# TopLevel.net
KiCad netlist of a schematic drawn in Altium Designer
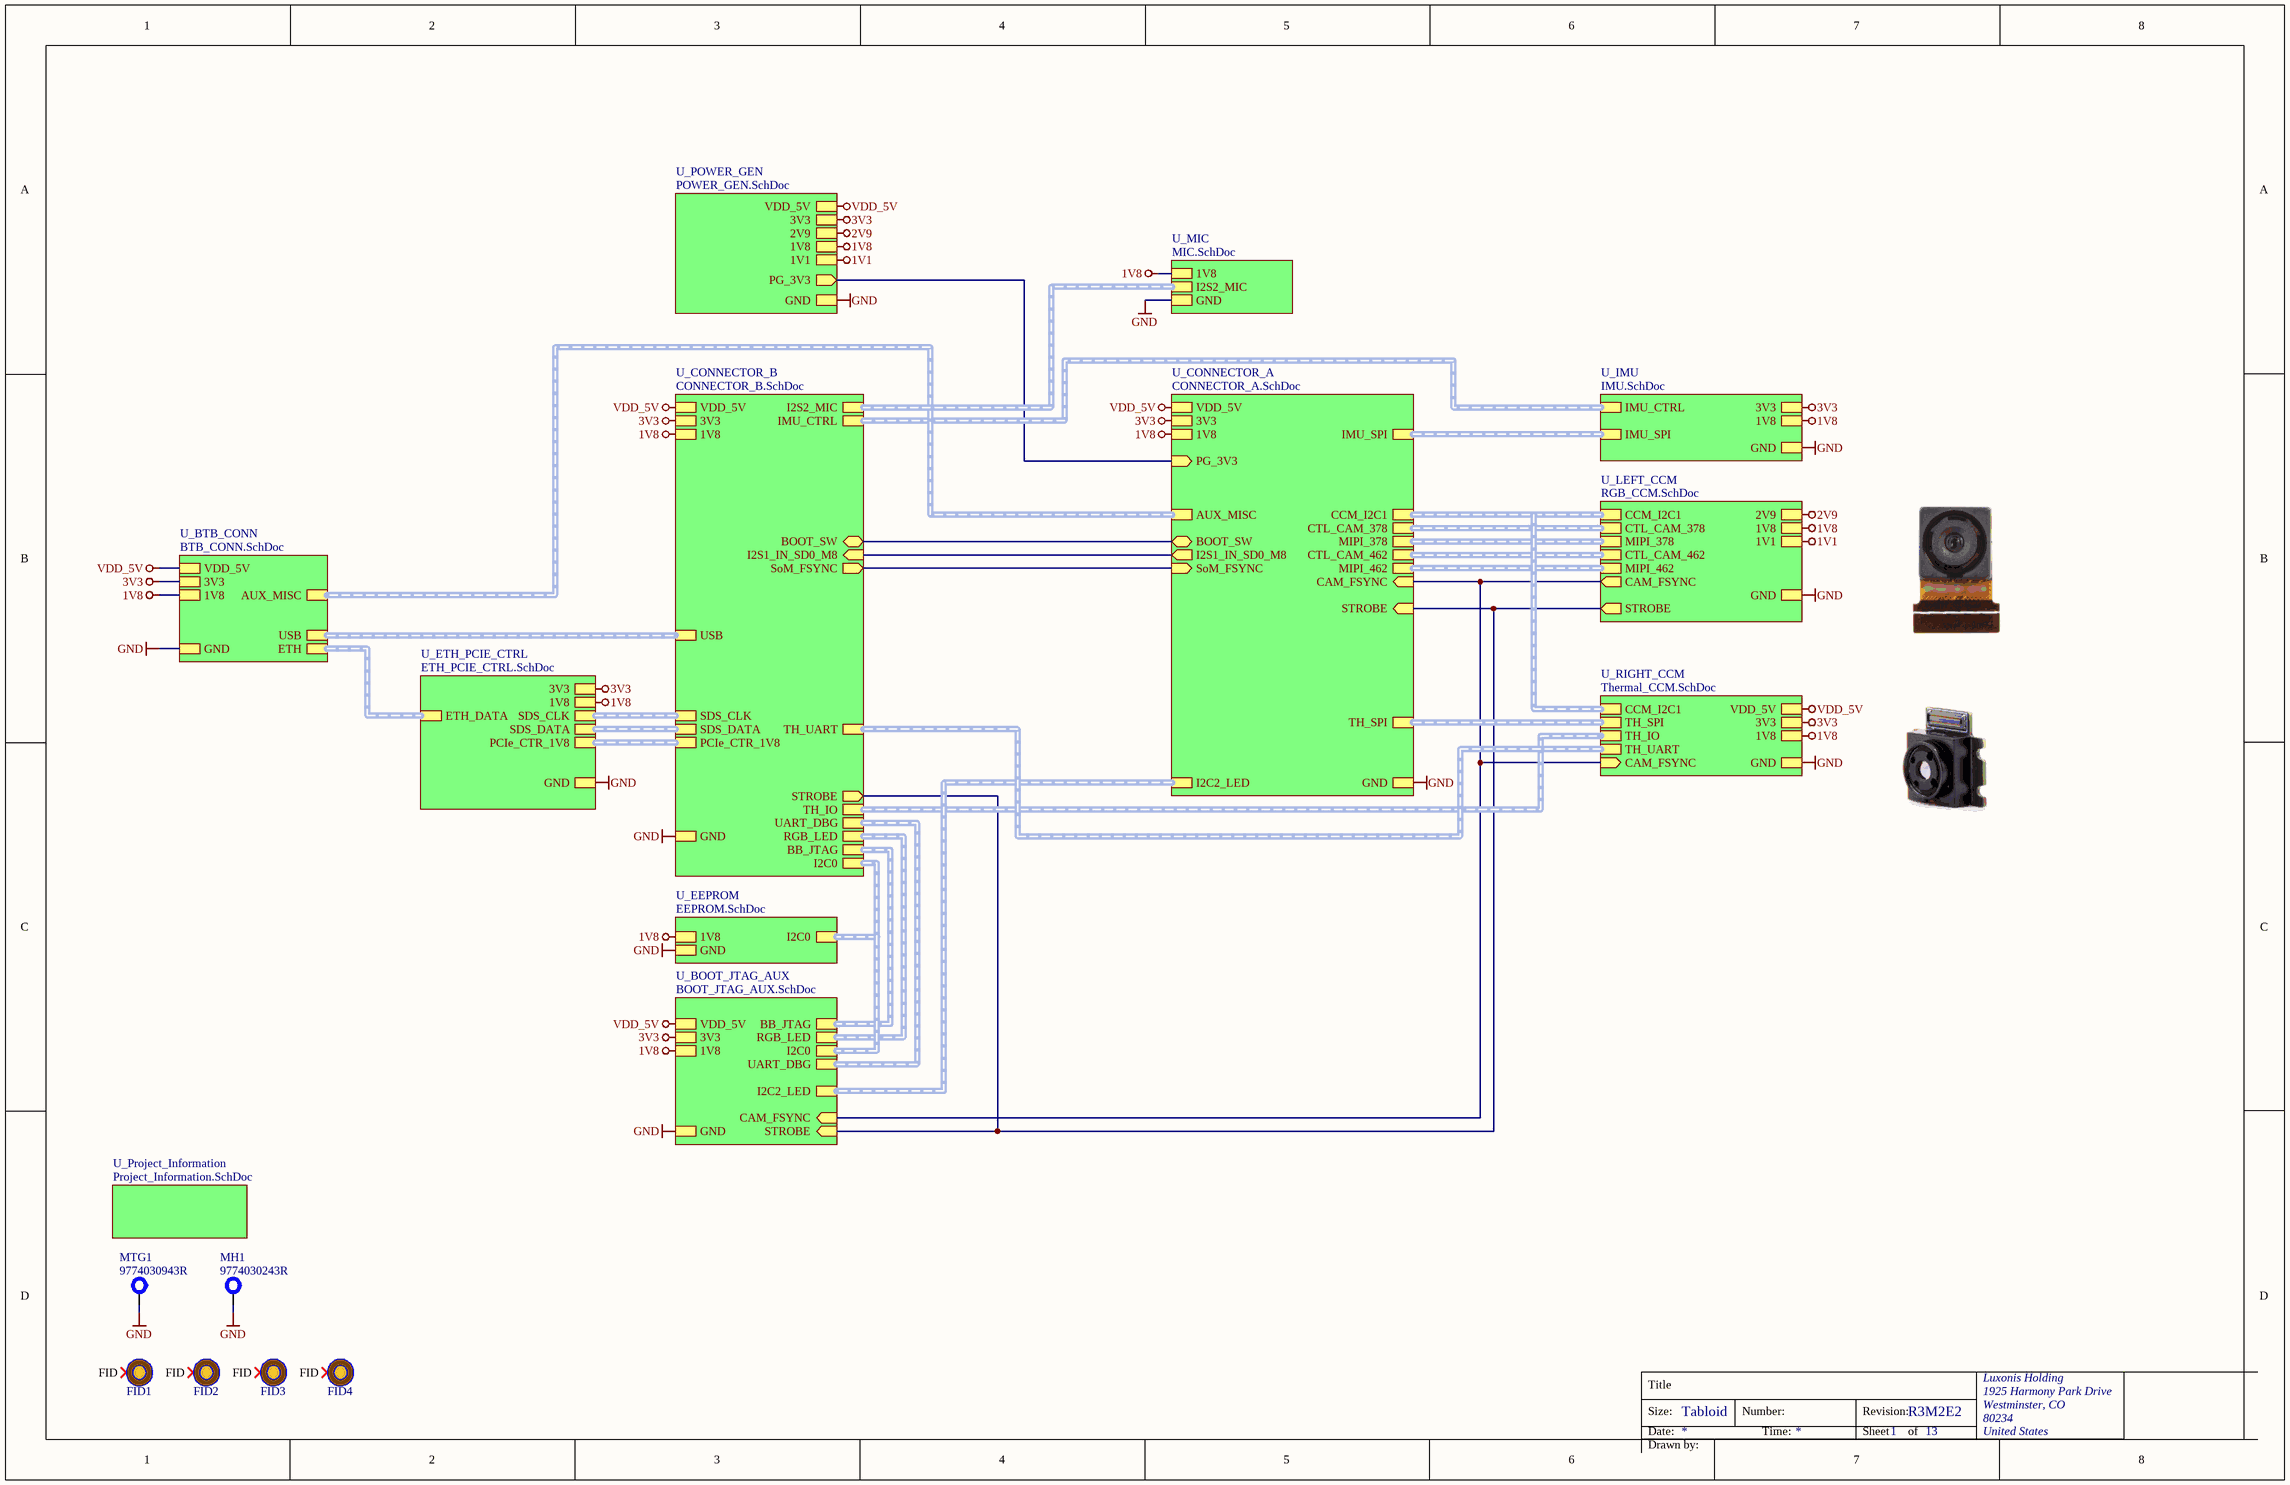
[diagram p0: TopLevel.SchDoc]

(export (version "E")
  (design (tool "Eeschema 10.0.6"))
  (components
    (comp (ref "FID1")
      (value "FIDUCIAL")
      (footprint "FIDUCIAL_ROUND_1MM")
      (description "Fiducial with various available footprints")
      (libsource (lib "Luxonis LLC") (part "FIDUCIAL"))
    )
    (comp (ref "FID2")
      (value "FIDUCIAL")
      (footprint "FIDUCIAL_ROUND_1MM")
      (description "Fiducial with various available footprints")
      (libsource (lib "Luxonis LLC") (part "FIDUCIAL"))
    )
    (comp (ref "FID3")
      (value "FIDUCIAL")
      (footprint "FIDUCIAL_ROUND_1MM")
      (description "Fiducial with various available footprints")
      (libsource (lib "Luxonis LLC") (part "FIDUCIAL"))
    )
    (comp (ref "FID4")
      (value "FIDUCIAL")
      (footprint "FIDUCIAL_ROUND_1MM")
      (description "Fiducial with various available footprints")
      (libsource (lib "Luxonis LLC") (part "FIDUCIAL"))
    )
    (comp (ref "MH1")
      (value "9774030243R")
      (footprint "9774030243R")
      (description "MP ROUND STANDOFF M2X0.4 STEEL 3MM")
      (libsource (lib "Luxonis LLC") (part "9774030243R"))
    )
    (comp (ref "MTG1")
      (value "9774030943R")
      (footprint "9774030943R")
      (description "Spacers/Standoffs")
      (libsource (lib "Luxonis LLC") (part "9774030943R"))
    )
  )
  (nets
    (net (code "33") (name "GND") (class "Default")
      (node (ref "MH1") (pin "1") (pintype "passive"))
      (node (ref "MTG1") (pin "1") (pintype "passive"))
    )
    (net (code "35") (name "unconnected-(FID1-PadFID)") (class "Default")
      (node (ref "FID1") (pin "FID") (pinfunction "FID_FID") (pintype "input+no_connect"))
    )
    (net (code "36") (name "unconnected-(FID2-PadFID)") (class "Default")
      (node (ref "FID2") (pin "FID") (pinfunction "FID_FID") (pintype "input+no_connect"))
    )
    (net (code "37") (name "unconnected-(FID3-PadFID)") (class "Default")
      (node (ref "FID3") (pin "FID") (pinfunction "FID_FID") (pintype "input+no_connect"))
    )
    (net (code "38") (name "unconnected-(FID4-PadFID)") (class "Default")
      (node (ref "FID4") (pin "FID") (pinfunction "FID_FID") (pintype "input+no_connect"))
    )
  )
)
